# ISL6236_V01_Schematic.net
KiCad netlist of a schematic drawn in Altium Designer
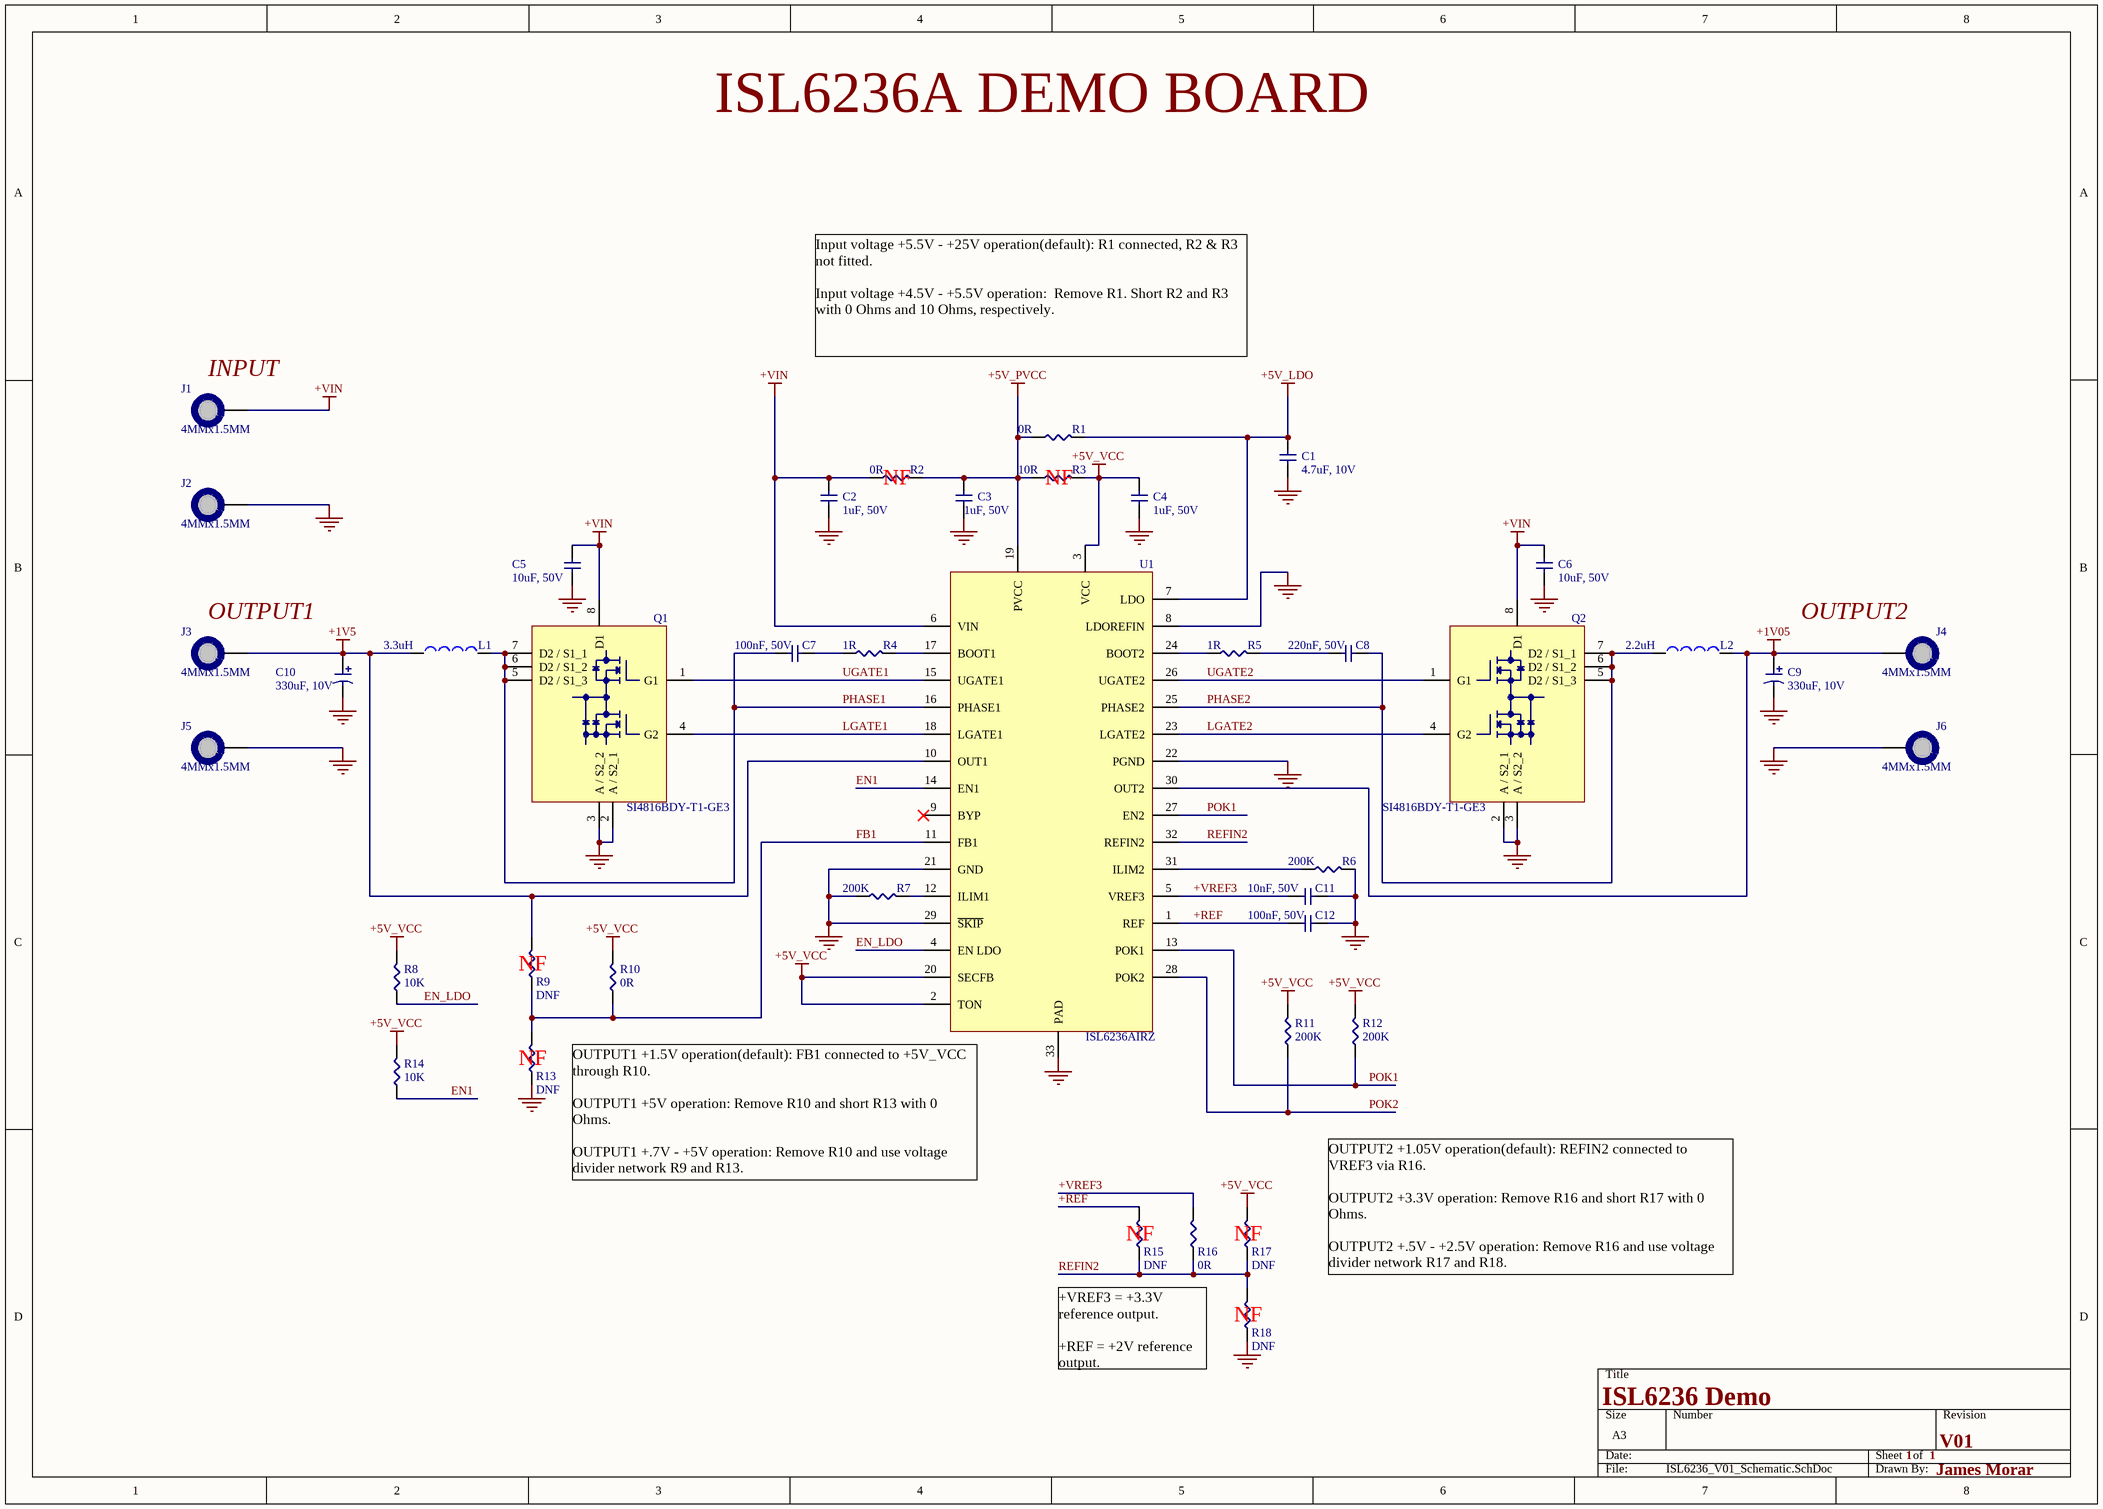
[diagram p0: ISL6236_V01_Schematic.SchDoc]

(export (version "E")
  (design (tool "Eeschema 10.0.6"))
  (components
    (comp (ref "C1")
      (value "4.7uF, 10V")
      (footprint "C1206")
      (fields
        (field (name "MANUFACTURER") "KEMET")
        (field (name "MANUFACTURER PART NUMBER") "C1206C475K8PACTU")
        (field (name "TOLERANCE") "-10, +10 %")
      )
      (libsource (lib "ISL6236_V01") (part "C1206C475K8PACTU"))
    )
    (comp (ref "C2")
      (value "1uF, 50V")
      (footprint "C0805")
      (fields
        (field (name "MANUFACTURER") "Kyocera AVX")
        (field (name "MANUFACTURER PART NUMBER") "08055C105KAZ4A")
      )
      (libsource (lib "ISL6236_V01") (part "08055C105KAZ4A"))
    )
    (comp (ref "C3")
      (value "1uF, 50V")
      (footprint "C0805")
      (fields
        (field (name "MANUFACTURER") "Kyocera AVX")
        (field (name "MANUFACTURER PART NUMBER") "08055C105KAZ4A")
      )
      (libsource (lib "ISL6236_V01") (part "08055C105KAZ4A"))
    )
    (comp (ref "C4")
      (value "1uF, 50V")
      (footprint "C0805")
      (fields
        (field (name "MANUFACTURER") "Kyocera AVX")
        (field (name "MANUFACTURER PART NUMBER") "08055C105KAZ4A")
      )
      (libsource (lib "ISL6236_V01") (part "08055C105KAZ4A"))
    )
    (comp (ref "C5")
      (value "10uF, 50V")
      (footprint "C1210")
      (fields
        (field (name "MANUFACTURER") "KEMET")
        (field (name "MANUFACTURER PART NUMBER") "C1210C106K5PACTU")
        (field (name "TOLERANCE") "±10%")
      )
      (libsource (lib "ISL6236_V01") (part "C1210C106K5PACTU"))
    )
    (comp (ref "C6")
      (value "10uF, 50V")
      (footprint "C1210")
      (fields
        (field (name "MANUFACTURER") "KEMET")
        (field (name "MANUFACTURER PART NUMBER") "C1210C106K5PACTU")
        (field (name "TOLERANCE") "±10%")
      )
      (libsource (lib "ISL6236_V01") (part "C1210C106K5PACTU"))
    )
    (comp (ref "C7")
      (value "100nF, 50V")
      (footprint "C0805")
      (description "Cap Ceramic 0.1uF 50V X7R 10% SMD 0805 125C Paper T/R")
      (fields
        (field (name "MANUFACTURER") "KEMET")
        (field (name "MANUFACTURER PART NUMBER") "C0805C104K5RAC7411")
      )
      (libsource (lib "ISL6236_V01") (part "C0805C104K5RAC7411"))
    )
    (comp (ref "C8")
      (value "220nF, 50V")
      (footprint "C0805")
      (description "Cap Ceramic 0.22uF 50V X7R 10% SMD 0805 125°C Embossed Plastic T/R")
      (fields
        (field (name "MANUFACTURER") "KEMET")
        (field (name "MANUFACTURER PART NUMBER") "C0805F224K5RACAUTO")
      )
      (libsource (lib "ISL6236_V01") (part "C0805F224K5RACAUTO"))
    )
    (comp (ref "C9")
      (value "330uF, 10V")
      (footprint "7343-43")
      (description "Tantalum Capacitors - Polymer SMD 330uF 10volts 20%")
      (fields
        (field (name "MANUFACTURER") "KEMET")
        (field (name "MANUFACTURER PART NUMBER") "T530X337M010ATE004")
      )
      (libsource (lib "ISL6236_V01") (part "T530X337M010ATE004"))
    )
    (comp (ref "C10")
      (value "330uF, 10V")
      (footprint "7343-43")
      (description "Tantalum Capacitors - Polymer SMD 330uF 10volts 20%")
      (fields
        (field (name "MANUFACTURER") "KEMET")
        (field (name "MANUFACTURER PART NUMBER") "T530X337M010ATE004")
      )
      (libsource (lib "ISL6236_V01") (part "T530X337M010ATE004"))
    )
    (comp (ref "C11")
      (value "10nF, 50V")
      (footprint "C0805")
      (description "Cap, 0.01?F, 50V, 10%, X7R, 0805")
      (fields
        (field (name "MANUFACTURER") "KEMET")
        (field (name "MANUFACTURER PART NUMBER") "C0805X103K5RAC7210")
      )
      (libsource (lib "ISL6236_V01") (part "C0805X103K5RAC7210"))
    )
    (comp (ref "C12")
      (value "100nF, 50V")
      (footprint "C0805")
      (description "Cap Ceramic 0.1uF 50V X7R 10% SMD 0805 125C Paper T/R")
      (fields
        (field (name "MANUFACTURER") "KEMET")
        (field (name "MANUFACTURER PART NUMBER") "C0805C104K5RAC7411")
      )
      (libsource (lib "ISL6236_V01") (part "C0805C104K5RAC7411"))
    )
    (comp (ref "J1")
      (value "4MMx1.5MM")
      (footprint "PAD_4MMx1.5MM")
      (description "4MMx1.5MM pad")
      (libsource (lib "ISL6236_V01") (part "PAD_4MMx1.5MM"))
    )
    (comp (ref "J2")
      (value "4MMx1.5MM")
      (footprint "PAD_4MMx1.5MM")
      (description "4MMx1.5MM pad")
      (libsource (lib "ISL6236_V01") (part "PAD_4MMx1.5MM"))
    )
    (comp (ref "J3")
      (value "4MMx1.5MM")
      (footprint "PAD_4MMx1.5MM")
      (description "4MMx1.5MM pad")
      (libsource (lib "ISL6236_V01") (part "PAD_4MMx1.5MM"))
    )
    (comp (ref "J4")
      (value "4MMx1.5MM")
      (footprint "PAD_4MMx1.5MM")
      (description "4MMx1.5MM pad")
      (libsource (lib "ISL6236_V01") (part "PAD_4MMx1.5MM"))
    )
    (comp (ref "J5")
      (value "4MMx1.5MM")
      (footprint "PAD_4MMx1.5MM")
      (description "4MMx1.5MM pad")
      (libsource (lib "ISL6236_V01") (part "PAD_4MMx1.5MM"))
    )
    (comp (ref "J6")
      (value "4MMx1.5MM")
      (footprint "PAD_4MMx1.5MM")
      (description "4MMx1.5MM pad")
      (libsource (lib "ISL6236_V01") (part "PAD_4MMx1.5MM"))
    )
    (comp (ref "L1")
      (value "3.3uH")
      (footprint "DR125")
      (description "FIXED IND 3.3UH 9.26A 6.3 MOHM")
      (fields
        (field (name "MANUFACTURER") "Eaton Cooper")
        (field (name "MANUFACTURER PART NUMBER") "DR125-3R3-R")
      )
      (libsource (lib "ISL6236_V01") (part "DR125-3R3-R"))
    )
    (comp (ref "L2")
      (value "2.2uH")
      (footprint "DR125")
      (description "FIXED IND 2.2UH 10.9A 4.5 MOHM")
      (fields
        (field (name "MANUFACTURER") "Eaton Cooper")
        (field (name "MANUFACTURER PART NUMBER") "DR125-2R2-R")
      )
      (libsource (lib "ISL6236_V01") (part "DR125-2R2-R"))
    )
    (comp (ref "Q1")
      (value "SI4816BDY-T1-GE3")
      (footprint "SO8")
      (description "MOSFET 2N-CH 30V 5.8A 8-SOIC")
      (fields (field (name "MANUFACTURER") "Vishay Siliconix"))
      (libsource (lib "") (part "SI4816BDY-T1-GE3_1"))
    )
    (comp (ref "Q2")
      (value "SI4816BDY-T1-GE3")
      (footprint "SO8")
      (description "MOSFET 2N-CH 30V 5.8A 8-SOIC")
      (fields (field (name "MANUFACTURER") "Vishay Siliconix"))
      (libsource (lib "ISL6236_V01") (part "SI4816BDY-T1-GE3"))
    )
    (comp (ref "R1")
      (value "0R")
      (footprint "R0805")
      (description "RES SMD 0 OHM JUMP 1/8W 0805")
      (fields
        (field (name "MANUFACTURER") "Vishay")
        (field (name "MANUFACTURER PART NUMBER") "CRCW08050000Z0EAC")
      )
      (libsource (lib "ISL6236_V01") (part "CRCW08050000Z0EAC"))
    )
    (comp (ref "R2")
      (value "0R")
      (footprint "R0805")
      (description "RES SMD 0 OHM JUMP 1/8W 0805")
      (fields
        (field (name "MANUFACTURER") "Vishay")
        (field (name "MANUFACTURER PART NUMBER") "CRCW08050000Z0EAC")
      )
      (libsource (lib "ISL6236_V01") (part "CRCW08050000Z0EAC"))
    )
    (comp (ref "R3")
      (value "10R")
      (footprint "R0805")
      (description "RES SMD 10 OHM 1% 1/8W 0805")
      (fields
        (field (name "MANUFACTURER") "Vishay")
        (field (name "MANUFACTURER PART NUMBER") "CRCW080510R0FKEAC")
      )
      (libsource (lib "ISL6236_V01") (part "CRCW080510R0FKEAC"))
    )
    (comp (ref "R4")
      (value "1R")
      (footprint "R0805")
      (description "Res Thick Film 0805 1 Ohm 1% 1/3W ±200ppm/°C Molded SMD SMD Punched Carrier T/R")
      (fields
        (field (name "MANUFACTURER") "Panasonic")
        (field (name "MANUFACTURER PART NUMBER") "ERJ-6BQF1R0V")
      )
      (libsource (lib "ISL6236_V01") (part "ERJ-6BQF1R0V"))
    )
    (comp (ref "R5")
      (value "1R")
      (footprint "R0805")
      (description "Res Thick Film 0805 1 Ohm 1% 1/3W ±200ppm/°C Molded SMD SMD Punched Carrier T/R")
      (fields
        (field (name "MANUFACTURER") "Panasonic")
        (field (name "MANUFACTURER PART NUMBER") "ERJ-6BQF1R0V")
      )
      (libsource (lib "ISL6236_V01") (part "ERJ-6BQF1R0V"))
    )
    (comp (ref "R6")
      (value "200K")
      (footprint "R0805")
      (fields
        (field (name "MANUFACTURER") "Panasonic")
        (field (name "MANUFACTURER PART NUMBER") "ERJ-S06F2003V")
        (field (name "TOLERANCE") "±1%")
      )
      (libsource (lib "ISL6236_V01") (part "ERJ-S06F2003V"))
    )
    (comp (ref "R7")
      (value "200K")
      (footprint "R0805")
      (fields
        (field (name "MANUFACTURER") "Panasonic")
        (field (name "MANUFACTURER PART NUMBER") "ERJ-S06F2003V")
        (field (name "TOLERANCE") "±1%")
      )
      (libsource (lib "ISL6236_V01") (part "ERJ-S06F2003V"))
    )
    (comp (ref "R8")
      (value "10K")
      (footprint "R0805")
      (description "RES SMD 10K OHM 1% 1/8W 0805")
      (fields
        (field (name "MANUFACTURER") "Vishay")
        (field (name "MANUFACTURER PART NUMBER") "CRCW080510K0FKEAC")
      )
      (libsource (lib "ISL6236_V01") (part "CRCW080510K0FKEAC"))
    )
    (comp (ref "R9") (value "DNF") (footprint "R0805") (libsource (lib "ISL6236_V01") (part "RES")))
    (comp (ref "R10")
      (value "0R")
      (footprint "R0805")
      (description "RES SMD 0 OHM JUMP 1/8W 0805")
      (fields
        (field (name "MANUFACTURER") "Vishay")
        (field (name "MANUFACTURER PART NUMBER") "CRCW08050000Z0EAC")
      )
      (libsource (lib "ISL6236_V01") (part "CRCW08050000Z0EAC"))
    )
    (comp (ref "R11")
      (value "200K")
      (footprint "R0805")
      (fields
        (field (name "MANUFACTURER") "Panasonic")
        (field (name "MANUFACTURER PART NUMBER") "ERJ-S06F2003V")
        (field (name "TOLERANCE") "±1%")
      )
      (libsource (lib "ISL6236_V01") (part "ERJ-S06F2003V"))
    )
    (comp (ref "R12")
      (value "200K")
      (footprint "R0805")
      (fields
        (field (name "MANUFACTURER") "Panasonic")
        (field (name "MANUFACTURER PART NUMBER") "ERJ-S06F2003V")
        (field (name "TOLERANCE") "±1%")
      )
      (libsource (lib "ISL6236_V01") (part "ERJ-S06F2003V"))
    )
    (comp (ref "R13") (value "DNF") (footprint "R0805") (libsource (lib "ISL6236_V01") (part "RES")))
    (comp (ref "R14")
      (value "10K")
      (footprint "R0805")
      (description "RES SMD 10K OHM 1% 1/8W 0805")
      (fields
        (field (name "MANUFACTURER") "Vishay")
        (field (name "MANUFACTURER PART NUMBER") "CRCW080510K0FKEAC")
      )
      (libsource (lib "ISL6236_V01") (part "CRCW080510K0FKEAC"))
    )
    (comp (ref "R15") (value "DNF") (footprint "R0805") (libsource (lib "ISL6236_V01") (part "RES")))
    (comp (ref "R16")
      (value "0R")
      (footprint "R0805")
      (description "RES SMD 0 OHM JUMP 1/8W 0805")
      (fields
        (field (name "MANUFACTURER") "Vishay")
        (field (name "MANUFACTURER PART NUMBER") "CRCW08050000Z0EAC")
      )
      (libsource (lib "ISL6236_V01") (part "CRCW08050000Z0EAC"))
    )
    (comp (ref "R17") (value "DNF") (footprint "R0805") (libsource (lib "ISL6236_V01") (part "RES")))
    (comp (ref "R18") (value "DNF") (footprint "R0805") (libsource (lib "ISL6236_V01") (part "RES")))
    (comp (ref "U1")
      (value "ISL6236AIRZ")
      (footprint "ISL6236_LQFN32")
      (description "IC MAIN PWR CTRLR QUAD 32-QFN")
      (fields (field (name "MANUFACTURER") "Renesas") (field (name "BASE PART NUMBER") "ISL6236"))
      (libsource (lib "ISL6236_V01") (part "ISL6236AIRZ"))
    )
  )
  (nets
    (net (code "1") (name "+1V5") (class "Default")
      (node (ref "C10") (pin "1") (pinfunction "1_1") (pintype "passive"))
      (node (ref "J3") (pin "1") (pinfunction "1_1") (pintype "passive"))
      (node (ref "L1") (pin "1") (pinfunction "1_1") (pintype "passive"))
      (node (ref "R9") (pin "2") (pinfunction "2_2") (pintype "passive"))
      (node (ref "U1") (pin "10") (pinfunction "OUT1_10") (pintype "passive"))
    )
    (net (code "2") (name "+1V05") (class "Default")
      (node (ref "C9") (pin "1") (pinfunction "1_1") (pintype "passive"))
      (node (ref "J4") (pin "1") (pinfunction "1_1") (pintype "passive"))
      (node (ref "L2") (pin "2") (pinfunction "2_2") (pintype "passive"))
      (node (ref "U1") (pin "30") (pinfunction "OUT2_30") (pintype "passive"))
    )
    (net (code "3") (name "+5V_LDO") (class "Default")
      (node (ref "C1") (pin "2") (pinfunction "2_2") (pintype "passive"))
      (node (ref "R1") (pin "2") (pinfunction "2_2") (pintype "passive"))
      (node (ref "U1") (pin "7") (pinfunction "LDO_7") (pintype "passive"))
    )
    (net (code "4") (name "+5V_PVCC") (class "Default")
      (node (ref "C3") (pin "2") (pinfunction "2_2") (pintype "passive"))
      (node (ref "R1") (pin "1") (pinfunction "1_1") (pintype "passive"))
      (node (ref "R2") (pin "2") (pinfunction "2_2") (pintype "passive"))
      (node (ref "R3") (pin "1") (pinfunction "1_1") (pintype "passive"))
      (node (ref "U1") (pin "19") (pinfunction "PVCC_19") (pintype "passive"))
    )
    (net (code "5") (name "+5V_VCC") (class "Default")
      (node (ref "C4") (pin "2") (pinfunction "2_2") (pintype "passive"))
      (node (ref "R10") (pin "2") (pinfunction "2_2") (pintype "passive"))
      (node (ref "R11") (pin "2") (pinfunction "2_2") (pintype "passive"))
      (node (ref "R12") (pin "1") (pinfunction "1_1") (pintype "passive"))
      (node (ref "R14") (pin "2") (pinfunction "2_2") (pintype "passive"))
      (node (ref "R17") (pin "2") (pinfunction "2_2") (pintype "passive"))
      (node (ref "R3") (pin "2") (pinfunction "2_2") (pintype "passive"))
      (node (ref "R8") (pin "2") (pinfunction "2_2") (pintype "passive"))
      (node (ref "U1") (pin "2") (pinfunction "TON_2") (pintype "passive"))
      (node (ref "U1") (pin "20") (pinfunction "SECFB_20") (pintype "passive"))
      (node (ref "U1") (pin "3") (pinfunction "VCC_3") (pintype "passive"))
    )
    (net (code "6") (name "+VIN") (class "Default")
      (node (ref "C2") (pin "2") (pinfunction "2_2") (pintype "passive"))
      (node (ref "C5") (pin "2") (pinfunction "2_2") (pintype "passive"))
      (node (ref "C6") (pin "2") (pinfunction "2_2") (pintype "passive"))
      (node (ref "J1") (pin "1") (pinfunction "1_1") (pintype "passive"))
      (node (ref "Q1") (pin "8") (pinfunction "D1_8") (pintype "passive"))
      (node (ref "Q2") (pin "8") (pinfunction "D1_8") (pintype "passive"))
      (node (ref "R2") (pin "1") (pinfunction "1_1") (pintype "passive"))
      (node (ref "U1") (pin "6") (pinfunction "VIN_6") (pintype "passive"))
    )
    (net (code "7") (name "/+REF") (class "Default")
      (node (ref "C12") (pin "1") (pinfunction "1_1") (pintype "passive"))
      (node (ref "R15") (pin "2") (pinfunction "2_2") (pintype "passive"))
      (node (ref "U1") (pin "1") (pinfunction "REF_1") (pintype "passive"))
    )
    (net (code "8") (name "/+VREF3") (class "Default")
      (node (ref "C11") (pin "1") (pinfunction "1_1") (pintype "passive"))
      (node (ref "R16") (pin "2") (pinfunction "2_2") (pintype "passive"))
      (node (ref "U1") (pin "5") (pinfunction "VREF3_5") (pintype "passive"))
    )
    (net (code "9") (name "/EN1") (class "Default")
      (node (ref "R14") (pin "1") (pinfunction "1_1") (pintype "passive"))
      (node (ref "U1") (pin "14") (pinfunction "EN1_14") (pintype "passive"))
    )
    (net (code "10") (name "/EN_LDO") (class "Default")
      (node (ref "R8") (pin "1") (pinfunction "1_1") (pintype "passive"))
      (node (ref "U1") (pin "4") (pinfunction "EN_LDO_4") (pintype "passive"))
    )
    (net (code "11") (name "/FB1") (class "Default")
      (node (ref "R10") (pin "1") (pinfunction "1_1") (pintype "passive"))
      (node (ref "R13") (pin "2") (pinfunction "2_2") (pintype "passive"))
      (node (ref "R9") (pin "1") (pinfunction "1_1") (pintype "passive"))
      (node (ref "U1") (pin "11") (pinfunction "FB1_11") (pintype "passive"))
    )
    (net (code "12") (name "/LGATE1") (class "Default")
      (node (ref "Q1") (pin "4") (pinfunction "G2_4") (pintype "passive"))
      (node (ref "U1") (pin "18") (pinfunction "LGATE1_18") (pintype "passive"))
    )
    (net (code "13") (name "/LGATE2") (class "Default")
      (node (ref "Q2") (pin "4") (pinfunction "G2_4") (pintype "passive"))
      (node (ref "U1") (pin "23") (pinfunction "LGATE2_23") (pintype "passive"))
    )
    (net (code "14") (name "/PHASE1") (class "Default")
      (node (ref "C7") (pin "2") (pinfunction "2_2") (pintype "passive"))
      (node (ref "L1") (pin "2") (pinfunction "2_2") (pintype "passive"))
      (node (ref "Q1") (pin "5") (pinfunction "D2_/_S1_3_5") (pintype "passive"))
      (node (ref "Q1") (pin "6") (pinfunction "D2_/_S1_2_6") (pintype "passive"))
      (node (ref "Q1") (pin "7") (pinfunction "D2_/_S1_1_7") (pintype "passive"))
      (node (ref "U1") (pin "16") (pinfunction "PHASE1_16") (pintype "passive"))
    )
    (net (code "15") (name "/PHASE2") (class "Default")
      (node (ref "C8") (pin "1") (pinfunction "1_1") (pintype "passive"))
      (node (ref "L2") (pin "1") (pinfunction "1_1") (pintype "passive"))
      (node (ref "Q2") (pin "5") (pinfunction "D2_/_S1_3_5") (pintype "passive"))
      (node (ref "Q2") (pin "6") (pinfunction "D2_/_S1_2_6") (pintype "passive"))
      (node (ref "Q2") (pin "7") (pinfunction "D2_/_S1_1_7") (pintype "passive"))
      (node (ref "U1") (pin "25") (pinfunction "PHASE2_25") (pintype "passive"))
    )
    (net (code "16") (name "/POK1") (class "Default")
      (node (ref "R12") (pin "2") (pinfunction "2_2") (pintype "passive"))
      (node (ref "U1") (pin "13") (pinfunction "POK1_13") (pintype "passive"))
      (node (ref "U1") (pin "27") (pinfunction "EN2_27") (pintype "passive"))
    )
    (net (code "17") (name "/POK2") (class "Default")
      (node (ref "R11") (pin "1") (pinfunction "1_1") (pintype "passive"))
      (node (ref "U1") (pin "28") (pinfunction "POK2_28") (pintype "passive"))
    )
    (net (code "18") (name "/REFIN2") (class "Default")
      (node (ref "R15") (pin "1") (pinfunction "1_1") (pintype "passive"))
      (node (ref "R16") (pin "1") (pinfunction "1_1") (pintype "passive"))
      (node (ref "R17") (pin "1") (pinfunction "1_1") (pintype "passive"))
      (node (ref "R18") (pin "2") (pinfunction "2_2") (pintype "passive"))
      (node (ref "U1") (pin "32") (pinfunction "REFIN2_32") (pintype "passive"))
    )
    (net (code "19") (name "/UGATE1") (class "Default")
      (node (ref "Q1") (pin "1") (pinfunction "G1_1") (pintype "passive"))
      (node (ref "U1") (pin "15") (pinfunction "UGATE1_15") (pintype "passive"))
    )
    (net (code "20") (name "/UGATE2") (class "Default")
      (node (ref "Q2") (pin "1") (pinfunction "G1_1") (pintype "passive"))
      (node (ref "U1") (pin "26") (pinfunction "UGATE2_26") (pintype "passive"))
    )
    (net (code "21") (name "GND") (class "Default")
      (node (ref "C1") (pin "1") (pinfunction "1_1") (pintype "passive"))
      (node (ref "C10") (pin "2") (pinfunction "2_2") (pintype "passive"))
      (node (ref "C11") (pin "2") (pinfunction "2_2") (pintype "passive"))
      (node (ref "C12") (pin "2") (pinfunction "2_2") (pintype "passive"))
      (node (ref "C2") (pin "1") (pinfunction "1_1") (pintype "passive"))
      (node (ref "C3") (pin "1") (pinfunction "1_1") (pintype "passive"))
      (node (ref "C4") (pin "1") (pinfunction "1_1") (pintype "passive"))
      (node (ref "C5") (pin "1") (pinfunction "1_1") (pintype "passive"))
      (node (ref "C6") (pin "1") (pinfunction "1_1") (pintype "passive"))
      (node (ref "C9") (pin "2") (pinfunction "2_2") (pintype "passive"))
      (node (ref "J2") (pin "1") (pinfunction "1_1") (pintype "passive"))
      (node (ref "J5") (pin "1") (pinfunction "1_1") (pintype "passive"))
      (node (ref "J6") (pin "1") (pinfunction "1_1") (pintype "passive"))
      (node (ref "Q1") (pin "2") (pinfunction "A_/_S2_1_2") (pintype "passive"))
      (node (ref "Q1") (pin "3") (pinfunction "A_/_S2_2_3") (pintype "passive"))
      (node (ref "Q2") (pin "2") (pinfunction "A_/_S2_1_2") (pintype "passive"))
      (node (ref "Q2") (pin "3") (pinfunction "A_/_S2_2_3") (pintype "passive"))
      (node (ref "R13") (pin "1") (pinfunction "1_1") (pintype "passive"))
      (node (ref "R18") (pin "1") (pinfunction "1_1") (pintype "passive"))
      (node (ref "R6") (pin "2") (pinfunction "2_2") (pintype "passive"))
      (node (ref "R7") (pin "1") (pinfunction "1_1") (pintype "passive"))
      (node (ref "U1") (pin "21") (pinfunction "GND_21") (pintype "passive"))
      (node (ref "U1") (pin "22") (pinfunction "PGND_22") (pintype "passive"))
      (node (ref "U1") (pin "29") (pinfunction "~{SKIP}_29") (pintype "passive"))
      (node (ref "U1") (pin "33") (pinfunction "PAD_33") (pintype "passive"))
      (node (ref "U1") (pin "8") (pinfunction "LDOREFIN_8") (pintype "passive"))
    )
    (net (code "22") (name "Net-(C7-Pad1)") (class "Default")
      (node (ref "C7") (pin "1") (pinfunction "1_1") (pintype "passive"))
      (node (ref "R4") (pin "1") (pinfunction "1_1") (pintype "passive"))
    )
    (net (code "23") (name "Net-(C8-Pad2)") (class "Default")
      (node (ref "C8") (pin "2") (pinfunction "2_2") (pintype "passive"))
      (node (ref "R5") (pin "2") (pinfunction "2_2") (pintype "passive"))
    )
    (net (code "24") (name "Net-(U1-BOOT1)") (class "Default")
      (node (ref "R4") (pin "2") (pinfunction "2_2") (pintype "passive"))
      (node (ref "U1") (pin "17") (pinfunction "BOOT1_17") (pintype "passive"))
    )
    (net (code "25") (name "Net-(U1-BOOT2)") (class "Default")
      (node (ref "R5") (pin "1") (pinfunction "1_1") (pintype "passive"))
      (node (ref "U1") (pin "24") (pinfunction "BOOT2_24") (pintype "passive"))
    )
    (net (code "26") (name "Net-(U1-ILIM1)") (class "Default")
      (node (ref "R7") (pin "2") (pinfunction "2_2") (pintype "passive"))
      (node (ref "U1") (pin "12") (pinfunction "ILIM1_12") (pintype "passive"))
    )
    (net (code "27") (name "Net-(U1-ILIM2)") (class "Default")
      (node (ref "R6") (pin "1") (pinfunction "1_1") (pintype "passive"))
      (node (ref "U1") (pin "31") (pinfunction "ILIM2_31") (pintype "passive"))
    )
    (net (code "28") (name "unconnected-(U1-BYP-Pad9)") (class "Default")
      (node (ref "U1") (pin "9") (pinfunction "BYP_9") (pintype "passive+no_connect"))
    )
  )
)
